# Mosfet_2Hbridge.net
KiCad netlist of a schematic drawn in EAGLE
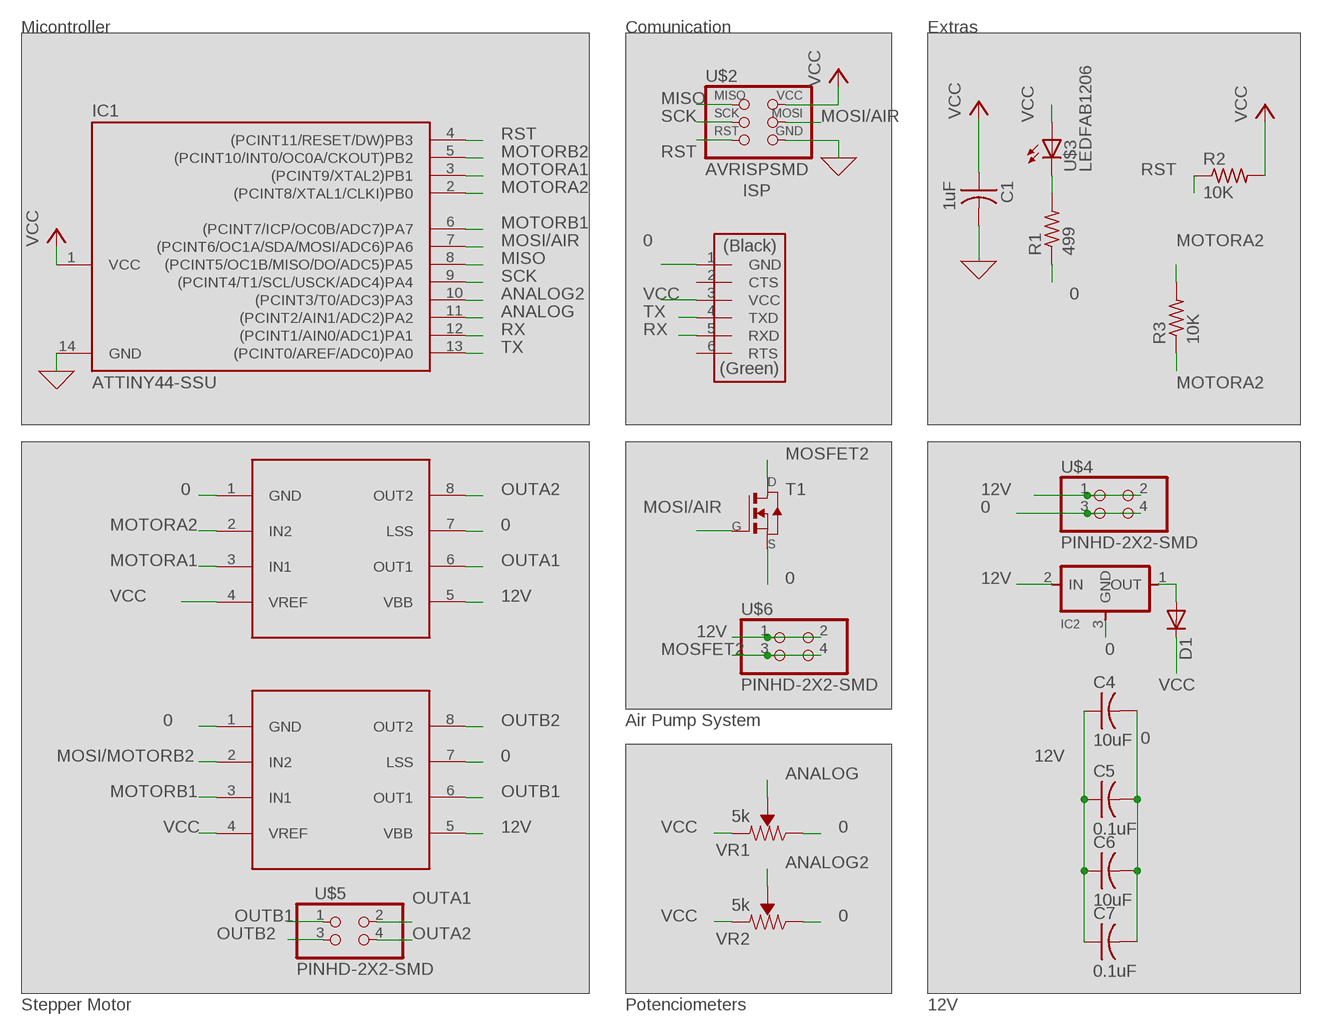
[diagram p0: schematic, sheet 1]

(export (version "E")
  (design (tool "Eeschema 10.0.6"))
  (components
    (comp (ref "C1")
      (value "1uF")
      (footprint "eagle-import:C1206FAB")
      (libsource (lib "eagle-import") (part "CAP-US1206FAB"))
    )
    (comp (ref "C4")
      (value "10uF")
      (footprint "eagle-import:C1206FAB")
      (libsource (lib "eagle-import") (part "CAP-US1206FAB"))
    )
    (comp (ref "C5")
      (value "0.1uF")
      (footprint "eagle-import:C1206FAB")
      (libsource (lib "eagle-import") (part "CAP-US1206FAB"))
    )
    (comp (ref "C6")
      (value "10uF")
      (footprint "eagle-import:C1206FAB")
      (libsource (lib "eagle-import") (part "CAP-US1206FAB"))
    )
    (comp (ref "C7")
      (value "0.1uF")
      (footprint "eagle-import:C1206FAB")
      (libsource (lib "eagle-import") (part "CAP-US1206FAB"))
    )
    (comp (ref "D1")
      (value "DIODESOD123")
      (footprint "eagle-import:SOD123")
      (libsource (lib "eagle-import") (part "DIODESOD123"))
    )
    (comp (ref "IC1")
      (value "ATTINY44-SSU")
      (footprint "eagle-import:SOIC14")
      (libsource (lib "eagle-import") (part "ATTINY44-SSU"))
    )
    (comp (ref "IC2")
      (value "REGULATORSOT23")
      (footprint "eagle-import:SOT23")
      (libsource (lib "eagle-import") (part "REGULATORSOT23"))
    )
    (comp (ref "R1")
      (value "499")
      (footprint "eagle-import:R1206FAB")
      (libsource (lib "eagle-import") (part "RES-US1206FAB"))
    )
    (comp (ref "R2")
      (value "10K")
      (footprint "eagle-import:R1206FAB")
      (libsource (lib "eagle-import") (part "RES-US1206FAB"))
    )
    (comp (ref "R3")
      (value "10K")
      (footprint "eagle-import:R1206FAB")
      (libsource (lib "eagle-import") (part "RES-US1206FAB"))
    )
    (comp (ref "T1")
      (value "NMOSFETTO252")
      (footprint "eagle-import:TO252")
      (libsource (lib "eagle-import") (part "NMOSFETTO252"))
    )
    (comp (ref "U$1")
      (value "FTDI-SMD-HEADER")
      (footprint "eagle-import:1X06SMD")
      (libsource (lib "eagle-import") (part "FTDI-SMD-HEADER"))
    )
    (comp (ref "U$2")
      (value "AVRISPSMD")
      (footprint "eagle-import:2X03SMD")
      (libsource (lib "eagle-import") (part "AVRISPSMD"))
    )
    (comp (ref "U$3")
      (value "LEDFAB1206")
      (footprint "eagle-import:LED1206FAB")
      (libsource (lib "eagle-import") (part "LEDFAB1206"))
    )
    (comp (ref "U$4")
      (value "PINHD-2X2-SMD")
      (footprint "eagle-import:2X02SMD")
      (libsource (lib "eagle-import") (part "PINHD-2X2-SMD"))
    )
    (comp (ref "U$5")
      (value "PINHD-2X2-SMD")
      (footprint "eagle-import:2X02SMD")
      (libsource (lib "eagle-import") (part "PINHD-2X2-SMD"))
    )
    (comp (ref "U$6")
      (value "PINHD-2X2-SMD")
      (footprint "eagle-import:2X02SMD")
      (libsource (lib "eagle-import") (part "PINHD-2X2-SMD"))
    )
    (comp (ref "U$7")
      (value "A4953-H-BRIDGE-MOTOR-DRIVER")
      (footprint "eagle-import:SOIC8")
      (libsource (lib "eagle-import") (part "A4953-H-BRIDGE-MOTOR-DRIVER"))
    )
    (comp (ref "U$8")
      (value "A4953-H-BRIDGE-MOTOR-DRIVER")
      (footprint "eagle-import:SOIC8")
      (libsource (lib "eagle-import") (part "A4953-H-BRIDGE-MOTOR-DRIVER"))
    )
    (comp (ref "VR1")
      (value "5k")
      (footprint "eagle-import:TRIMPOT-SMD-5MM")
      (libsource (lib "eagle-import") (part "TRIMPOT-SMD-5MM-CLOSED-1/4W-20%"))
    )
    (comp (ref "VR2")
      (value "5k")
      (footprint "eagle-import:TRIMPOT-SMD-5MM")
      (libsource (lib "eagle-import") (part "TRIMPOT-SMD-5MM-CLOSED-1/4W-20%"))
    )
  )
  (nets
    (net (code "1") (name "/12V") (class "Default")
      (node (ref "C4") (pin "1") (pinfunction "1_1") (pintype "passive"))
      (node (ref "C5") (pin "1") (pinfunction "1_1") (pintype "passive"))
      (node (ref "C6") (pin "1") (pinfunction "1_1") (pintype "passive"))
      (node (ref "C7") (pin "1") (pinfunction "1_1") (pintype "passive"))
      (node (ref "IC2") (pin "2") (pinfunction "IN_2") (pintype "bidirectional"))
      (node (ref "U$4") (pin "1") (pinfunction "1_1") (pintype "passive"))
      (node (ref "U$4") (pin "2") (pinfunction "2_2") (pintype "passive"))
      (node (ref "U$6") (pin "1") (pinfunction "1_1") (pintype "passive"))
      (node (ref "U$6") (pin "2") (pinfunction "2_2") (pintype "passive"))
      (node (ref "U$7") (pin "5") (pinfunction "VBB_5") (pintype "bidirectional"))
      (node (ref "U$8") (pin "5") (pinfunction "VBB_5") (pintype "bidirectional"))
    )
    (net (code "2") (name "/ANALOG") (class "Default")
      (node (ref "IC1") (pin "11") (pinfunction "(PCINT2/AIN1/ADC2)PA2_11") (pintype "bidirectional"))
      (node (ref "VR1") (pin "B") (pinfunction "WIPER_B") (pintype "passive"))
    )
    (net (code "3") (name "/ANALOG2") (class "Default")
      (node (ref "IC1") (pin "10") (pinfunction "(PCINT3/T0/ADC3)PA3_10") (pintype "bidirectional"))
      (node (ref "VR2") (pin "B") (pinfunction "WIPER_B") (pintype "passive"))
    )
    (net (code "4") (name "/MISO") (class "Default")
      (node (ref "IC1") (pin "8") (pinfunction "(PCINT5/OC1B/MISO/DO/ADC5)PA5_8") (pintype "bidirectional"))
      (node (ref "U$2") (pin "1") (pinfunction "MISO_1") (pintype "passive"))
    )
    (net (code "5") (name "/MOSFET2") (class "Default")
      (node (ref "T1") (pin "3") (pinfunction "D_3") (pintype "passive"))
      (node (ref "U$6") (pin "3") (pinfunction "3_3") (pintype "passive"))
      (node (ref "U$6") (pin "4") (pinfunction "4_4") (pintype "passive"))
    )
    (net (code "6") (name "/MOSI{slash}AIR") (class "Default")
      (node (ref "IC1") (pin "7") (pinfunction "(PCINT6/OC1A/SDA/MOSI/ADC6)PA6_7") (pintype "bidirectional"))
      (node (ref "T1") (pin "1") (pinfunction "G_1") (pintype "passive"))
      (node (ref "U$2") (pin "4") (pinfunction "MOSI_4") (pintype "passive"))
    )
    (net (code "7") (name "/MOSI{slash}MOTORB2") (class "Default")
      (node (ref "U$7") (pin "2") (pinfunction "IN2_2") (pintype "bidirectional"))
    )
    (net (code "8") (name "/MOTORA1") (class "Default")
      (node (ref "IC1") (pin "3") (pinfunction "(PCINT9/XTAL2)PB1_3") (pintype "bidirectional"))
      (node (ref "U$8") (pin "3") (pinfunction "IN1_3") (pintype "bidirectional"))
    )
    (net (code "9") (name "/MOTORA2") (class "Default")
      (node (ref "IC1") (pin "2") (pinfunction "(PCINT8/XTAL1/CLKI)PB0_2") (pintype "bidirectional"))
      (node (ref "R3") (pin "1") (pinfunction "1_1") (pintype "passive"))
      (node (ref "R3") (pin "2") (pinfunction "2_2") (pintype "passive"))
      (node (ref "U$8") (pin "2") (pinfunction "IN2_2") (pintype "bidirectional"))
    )
    (net (code "10") (name "/MOTORB1") (class "Default")
      (node (ref "IC1") (pin "6") (pinfunction "(PCINT7/ICP/OC0B/ADC7)PA7_6") (pintype "bidirectional"))
      (node (ref "U$7") (pin "3") (pinfunction "IN1_3") (pintype "bidirectional"))
    )
    (net (code "11") (name "/MOTORB2") (class "Default")
      (node (ref "IC1") (pin "5") (pinfunction "(PCINT10/INT0/OC0A/CKOUT)PB2_5") (pintype "bidirectional"))
    )
    (net (code "12") (name "/OUTA1") (class "Default")
      (node (ref "U$5") (pin "2") (pinfunction "2_2") (pintype "passive"))
      (node (ref "U$8") (pin "6") (pinfunction "OUT1_6") (pintype "bidirectional"))
    )
    (net (code "13") (name "/OUTA2") (class "Default")
      (node (ref "U$5") (pin "4") (pinfunction "4_4") (pintype "passive"))
      (node (ref "U$8") (pin "8") (pinfunction "OUT2_8") (pintype "bidirectional"))
    )
    (net (code "14") (name "/OUTB1") (class "Default")
      (node (ref "U$5") (pin "1") (pinfunction "1_1") (pintype "passive"))
      (node (ref "U$7") (pin "6") (pinfunction "OUT1_6") (pintype "bidirectional"))
    )
    (net (code "15") (name "/OUTB2") (class "Default")
      (node (ref "U$5") (pin "3") (pinfunction "3_3") (pintype "passive"))
      (node (ref "U$7") (pin "8") (pinfunction "OUT2_8") (pintype "bidirectional"))
    )
    (net (code "16") (name "/RST") (class "Default")
      (node (ref "IC1") (pin "4") (pinfunction "(PCINT11/RESET/DW)PB3_4") (pintype "bidirectional"))
      (node (ref "R2") (pin "1") (pinfunction "1_1") (pintype "passive"))
      (node (ref "U$2") (pin "5") (pinfunction "RST_5") (pintype "passive"))
    )
    (net (code "17") (name "/RX") (class "Default")
      (node (ref "IC1") (pin "12") (pinfunction "(PCINT1/AIN0/ADC1)PA1_12") (pintype "bidirectional"))
      (node (ref "U$1") (pin "5") (pinfunction "RXD_5") (pintype "bidirectional"))
    )
    (net (code "18") (name "/SCK") (class "Default")
      (node (ref "IC1") (pin "9") (pinfunction "(PCINT4/T1/SCL/USCK/ADC4)PA4_9") (pintype "bidirectional"))
      (node (ref "U$2") (pin "3") (pinfunction "SCK_3") (pintype "passive"))
    )
    (net (code "19") (name "/TX") (class "Default")
      (node (ref "IC1") (pin "13") (pinfunction "(PCINT0/AREF/ADC0)PA0_13") (pintype "bidirectional"))
      (node (ref "U$1") (pin "4") (pinfunction "TXD_4") (pintype "bidirectional"))
    )
    (net (code "20") (name "GND") (class "Default")
      (node (ref "C1") (pin "2") (pinfunction "2_2") (pintype "passive"))
      (node (ref "C4") (pin "2") (pinfunction "2_2") (pintype "passive"))
      (node (ref "C5") (pin "2") (pinfunction "2_2") (pintype "passive"))
      (node (ref "C6") (pin "2") (pinfunction "2_2") (pintype "passive"))
      (node (ref "C7") (pin "2") (pinfunction "2_2") (pintype "passive"))
      (node (ref "IC1") (pin "14") (pinfunction "GND_14") (pintype "power_in"))
      (node (ref "IC2") (pin "3") (pinfunction "GND_3") (pintype "bidirectional"))
      (node (ref "R1") (pin "1") (pinfunction "1_1") (pintype "passive"))
      (node (ref "T1") (pin "2") (pinfunction "S_2") (pintype "passive"))
      (node (ref "U$1") (pin "1") (pinfunction "GND_1") (pintype "bidirectional"))
      (node (ref "U$2") (pin "6") (pinfunction "GND_6") (pintype "passive"))
      (node (ref "U$4") (pin "3") (pinfunction "3_3") (pintype "passive"))
      (node (ref "U$4") (pin "4") (pinfunction "4_4") (pintype "passive"))
      (node (ref "U$7") (pin "1") (pinfunction "GND_1") (pintype "bidirectional"))
      (node (ref "U$7") (pin "7") (pinfunction "LSS_7") (pintype "bidirectional"))
      (node (ref "U$8") (pin "1") (pinfunction "GND_1") (pintype "bidirectional"))
      (node (ref "U$8") (pin "7") (pinfunction "LSS_7") (pintype "bidirectional"))
      (node (ref "VR1") (pin "C") (pinfunction "CW_C") (pintype "passive"))
      (node (ref "VR2") (pin "C") (pinfunction "CW_C") (pintype "passive"))
    )
    (net (code "21") (name "Net-(D1-A)") (class "Default")
      (node (ref "D1") (pin "ANODE") (pinfunction "A_ANODE") (pintype "passive"))
      (node (ref "IC2") (pin "1") (pinfunction "OUT_1") (pintype "bidirectional"))
    )
    (net (code "22") (name "Net-(U$3-C)") (class "Default")
      (node (ref "R1") (pin "2") (pinfunction "2_2") (pintype "passive"))
      (node (ref "U$3") (pin "2") (pinfunction "C_2") (pintype "passive"))
    )
    (net (code "23") (name "VCC") (class "Default")
      (node (ref "C1") (pin "1") (pinfunction "1_1") (pintype "passive"))
      (node (ref "D1") (pin "CATHODE") (pinfunction "C_CATHODE") (pintype "passive"))
      (node (ref "IC1") (pin "1") (pinfunction "VCC_1") (pintype "power_in"))
      (node (ref "R2") (pin "2") (pinfunction "2_2") (pintype "passive"))
      (node (ref "U$1") (pin "3") (pinfunction "VCC_3") (pintype "bidirectional"))
      (node (ref "U$2") (pin "2") (pinfunction "VCC_2") (pintype "passive"))
      (node (ref "U$3") (pin "1") (pinfunction "A_1") (pintype "passive"))
      (node (ref "U$7") (pin "4") (pinfunction "VREF_4") (pintype "bidirectional"))
      (node (ref "U$8") (pin "4") (pinfunction "VREF_4") (pintype "bidirectional"))
      (node (ref "VR1") (pin "A") (pinfunction "CCW_A") (pintype "passive"))
      (node (ref "VR2") (pin "A") (pinfunction "CCW_A") (pintype "passive"))
    )
    (net (code "24") (name "unconnected-(U$1-CTS-Pad2)") (class "Default")
      (node (ref "U$1") (pin "2") (pinfunction "CTS_2") (pintype "bidirectional"))
    )
    (net (code "25") (name "unconnected-(U$1-RTS-Pad6)") (class "Default")
      (node (ref "U$1") (pin "6") (pinfunction "RTS_6") (pintype "bidirectional"))
    )
  )
)
